# SMART2RGB.net
KiCad netlist of a schematic drawn in EAGLE
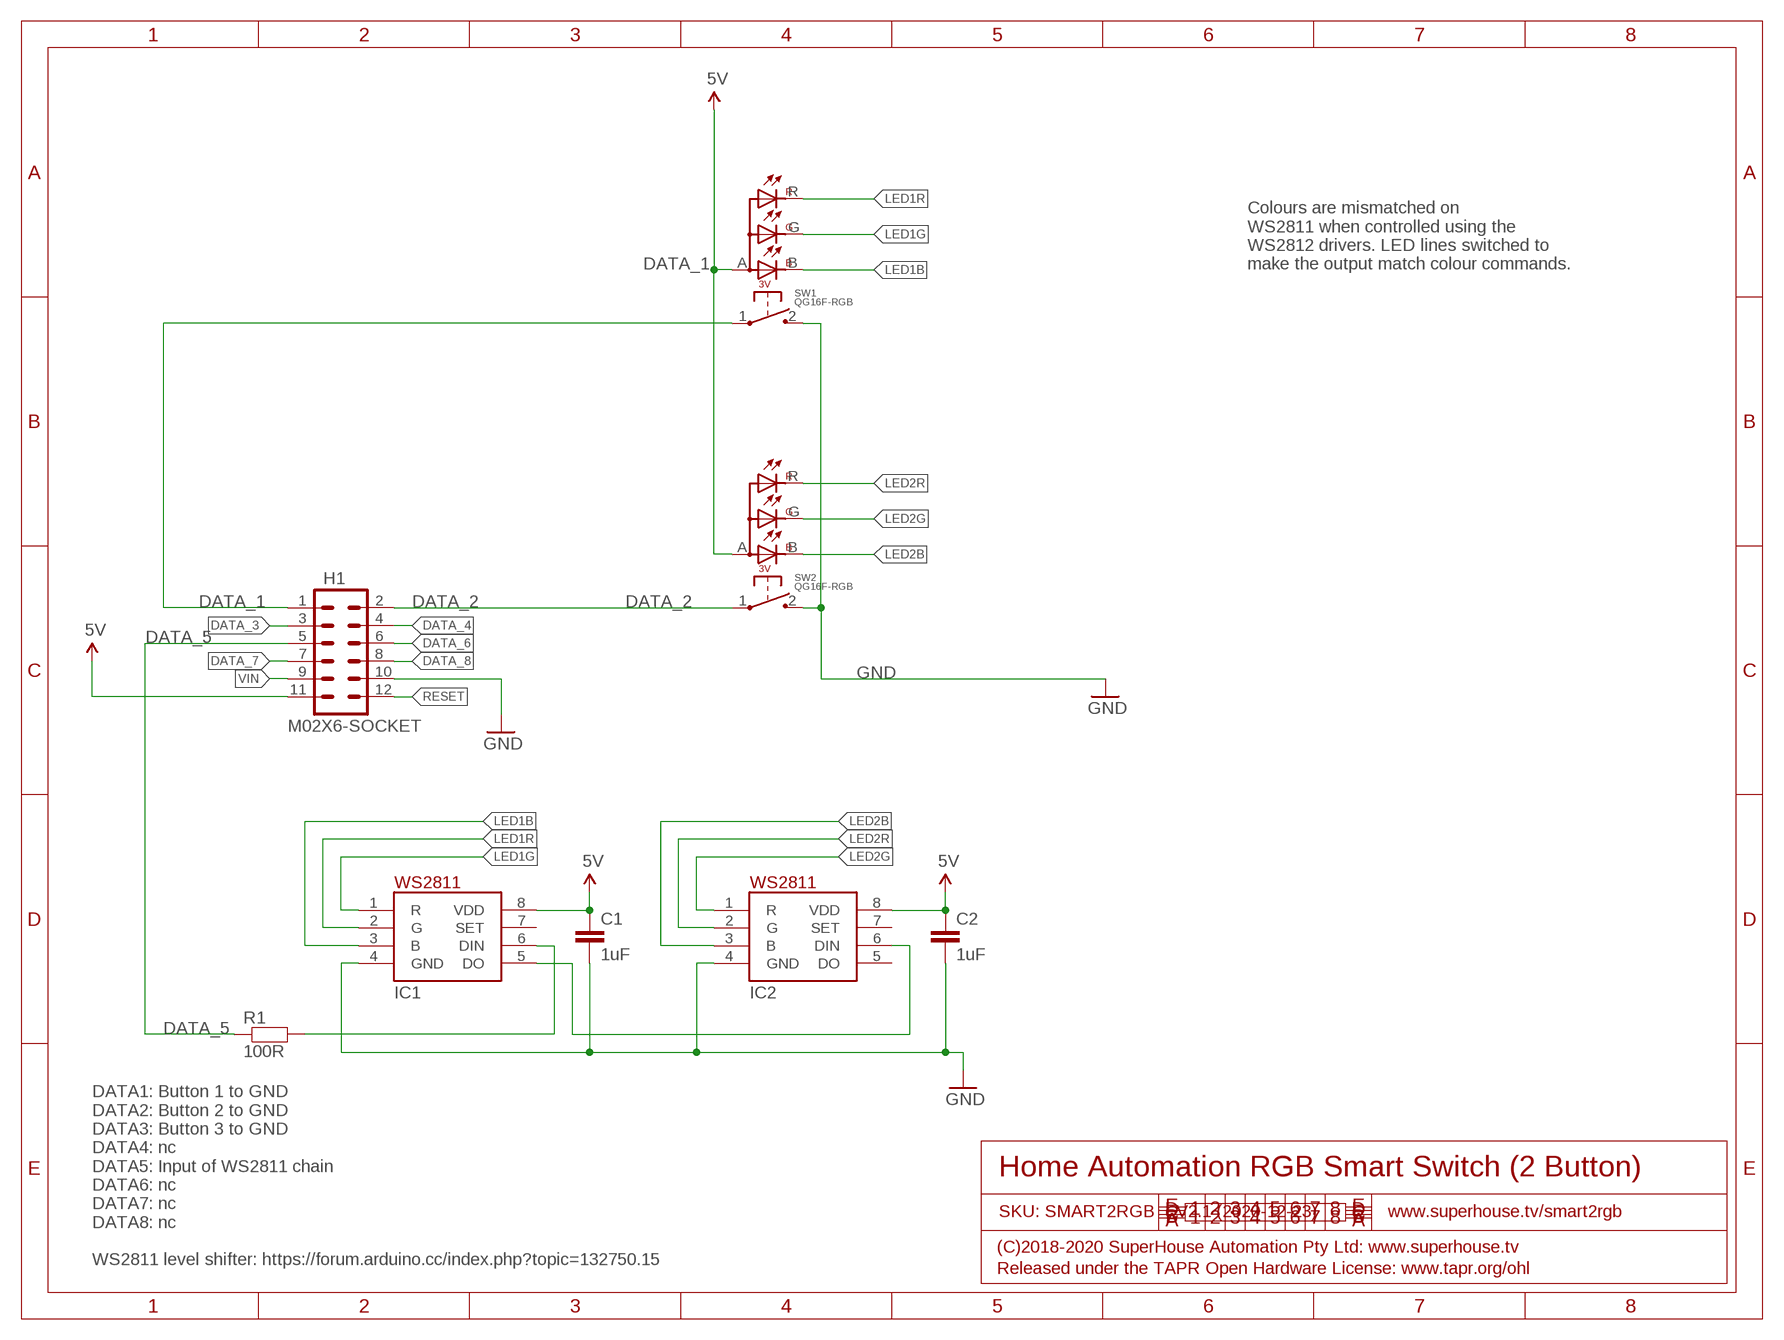
[diagram p0: schematic, sheet 1]

(export (version "E")
  (design (tool "Eeschema 10.0.6"))
  (components
    (comp (ref "C1")
      (value "1uF")
      (footprint "eagle-import:C0603")
      (libsource (lib "eagle-import") (part "CAP0603"))
    )
    (comp (ref "C2")
      (value "1uF")
      (footprint "eagle-import:C0603")
      (libsource (lib "eagle-import") (part "CAP0603"))
    )
    (comp (ref "H1")
      (value "M02X6-SOCKET")
      (footprint "eagle-import:2X06-S")
      (libsource (lib "eagle-import") (part "M02X6-SOCKET"))
    )
    (comp (ref "IC1")
      (value "WS2811-SOP8")
      (footprint "eagle-import:SO08-SKINNYPADS")
      (libsource (lib "eagle-import") (part "WS2811-SOP8"))
    )
    (comp (ref "IC2")
      (value "WS2811-SOP8")
      (footprint "eagle-import:SO08-SKINNYPADS")
      (libsource (lib "eagle-import") (part "WS2811-SOP8"))
    )
    (comp (ref "R1")
      (value "100R")
      (footprint "eagle-import:R0603")
      (libsource (lib "eagle-import") (part "RESISTOR0603"))
    )
    (comp (ref "SW1")
      (value "QG16F-RGB")
      (footprint "eagle-import:QG16F-RGB")
      (libsource (lib "eagle-import") (part "QG16F-RGB"))
    )
    (comp (ref "SW2")
      (value "QG16F-RGB")
      (footprint "eagle-import:QG16F-RGB")
      (libsource (lib "eagle-import") (part "QG16F-RGB"))
    )
  )
  (nets
    (net (code "1") (name "/DATA_1") (class "Default")
      (node (ref "H1") (pin "1") (pinfunction "1_1") (pintype "passive"))
      (node (ref "SW1") (pin "1") (pinfunction "1_1") (pintype "passive"))
    )
    (net (code "2") (name "/DATA_2") (class "Default")
      (node (ref "H1") (pin "2") (pinfunction "2_2") (pintype "passive"))
      (node (ref "SW2") (pin "1") (pinfunction "1_1") (pintype "passive"))
    )
    (net (code "3") (name "/DATA_5") (class "Default")
      (node (ref "H1") (pin "5") (pinfunction "5_5") (pintype "passive"))
      (node (ref "R1") (pin "1") (pinfunction "1_1") (pintype "passive"))
    )
    (net (code "4") (name "5V") (class "Default")
      (node (ref "C1") (pin "1") (pinfunction "1_1") (pintype "passive"))
      (node (ref "C2") (pin "1") (pinfunction "1_1") (pintype "passive"))
      (node (ref "H1") (pin "11") (pinfunction "11_11") (pintype "passive"))
      (node (ref "IC1") (pin "8") (pinfunction "VDD_8") (pintype "power_in"))
      (node (ref "IC2") (pin "8") (pinfunction "VDD_8") (pintype "power_in"))
      (node (ref "SW1") (pin "A") (pinfunction "+_A") (pintype "passive"))
      (node (ref "SW2") (pin "A") (pinfunction "+_A") (pintype "passive"))
    )
    (net (code "5") (name "DATA_3") (class "Default")
      (node (ref "H1") (pin "3") (pinfunction "3_3") (pintype "passive"))
    )
    (net (code "6") (name "DATA_4") (class "Default")
      (node (ref "H1") (pin "4") (pinfunction "4_4") (pintype "passive"))
    )
    (net (code "7") (name "DATA_6") (class "Default")
      (node (ref "H1") (pin "6") (pinfunction "6_6") (pintype "passive"))
    )
    (net (code "8") (name "DATA_7") (class "Default")
      (node (ref "H1") (pin "7") (pinfunction "7_7") (pintype "passive"))
    )
    (net (code "9") (name "DATA_8") (class "Default")
      (node (ref "H1") (pin "8") (pinfunction "8_8") (pintype "passive"))
    )
    (net (code "10") (name "GND") (class "Default")
      (node (ref "C1") (pin "2") (pinfunction "2_2") (pintype "passive"))
      (node (ref "C2") (pin "2") (pinfunction "2_2") (pintype "passive"))
      (node (ref "H1") (pin "10") (pinfunction "10_10") (pintype "passive"))
      (node (ref "IC1") (pin "4") (pinfunction "GND_4") (pintype "power_in"))
      (node (ref "IC2") (pin "4") (pinfunction "GND_4") (pintype "power_in"))
      (node (ref "SW1") (pin "2") (pinfunction "2_2") (pintype "passive"))
      (node (ref "SW2") (pin "2") (pinfunction "2_2") (pintype "passive"))
    )
    (net (code "11") (name "LED1B") (class "Default")
      (node (ref "IC1") (pin "3") (pinfunction "B_3") (pintype "open_collector"))
      (node (ref "SW1") (pin "B") (pinfunction "B_B") (pintype "passive"))
    )
    (net (code "12") (name "LED1G") (class "Default")
      (node (ref "IC1") (pin "1") (pinfunction "R_1") (pintype "open_collector"))
      (node (ref "SW1") (pin "G") (pinfunction "G_G") (pintype "passive"))
    )
    (net (code "13") (name "LED1R") (class "Default")
      (node (ref "IC1") (pin "2") (pinfunction "G_2") (pintype "open_collector"))
      (node (ref "SW1") (pin "R") (pinfunction "R_R") (pintype "passive"))
    )
    (net (code "14") (name "LED2B") (class "Default")
      (node (ref "IC2") (pin "3") (pinfunction "B_3") (pintype "open_collector"))
      (node (ref "SW2") (pin "B") (pinfunction "B_B") (pintype "passive"))
    )
    (net (code "15") (name "LED2G") (class "Default")
      (node (ref "IC2") (pin "1") (pinfunction "R_1") (pintype "open_collector"))
      (node (ref "SW2") (pin "G") (pinfunction "G_G") (pintype "passive"))
    )
    (net (code "16") (name "LED2R") (class "Default")
      (node (ref "IC2") (pin "2") (pinfunction "G_2") (pintype "open_collector"))
      (node (ref "SW2") (pin "R") (pinfunction "R_R") (pintype "passive"))
    )
    (net (code "17") (name "Net-(IC1-DIN)") (class "Default")
      (node (ref "IC1") (pin "6") (pinfunction "DIN_6") (pintype "input"))
      (node (ref "R1") (pin "2") (pinfunction "2_2") (pintype "passive"))
    )
    (net (code "18") (name "Net-(IC1-DO)") (class "Default")
      (node (ref "IC1") (pin "5") (pinfunction "DO_5") (pintype "output"))
      (node (ref "IC2") (pin "6") (pinfunction "DIN_6") (pintype "input"))
    )
    (net (code "19") (name "RESET") (class "Default")
      (node (ref "H1") (pin "12") (pinfunction "12_12") (pintype "passive"))
    )
    (net (code "20") (name "VIN") (class "Default")
      (node (ref "H1") (pin "9") (pinfunction "9_9") (pintype "passive"))
    )
    (net (code "21") (name "unconnected-(IC1-SET-Pad7)") (class "Default")
      (node (ref "IC1") (pin "7") (pinfunction "SET_7") (pintype "input"))
    )
    (net (code "22") (name "unconnected-(IC2-DO-Pad5)") (class "Default")
      (node (ref "IC2") (pin "5") (pinfunction "DO_5") (pintype "output"))
    )
    (net (code "23") (name "unconnected-(IC2-SET-Pad7)") (class "Default")
      (node (ref "IC2") (pin "7") (pinfunction "SET_7") (pintype "input"))
    )
  )
)
